# TLM_002_INA228.net
KiCad netlist of a schematic drawn in Altium Designer
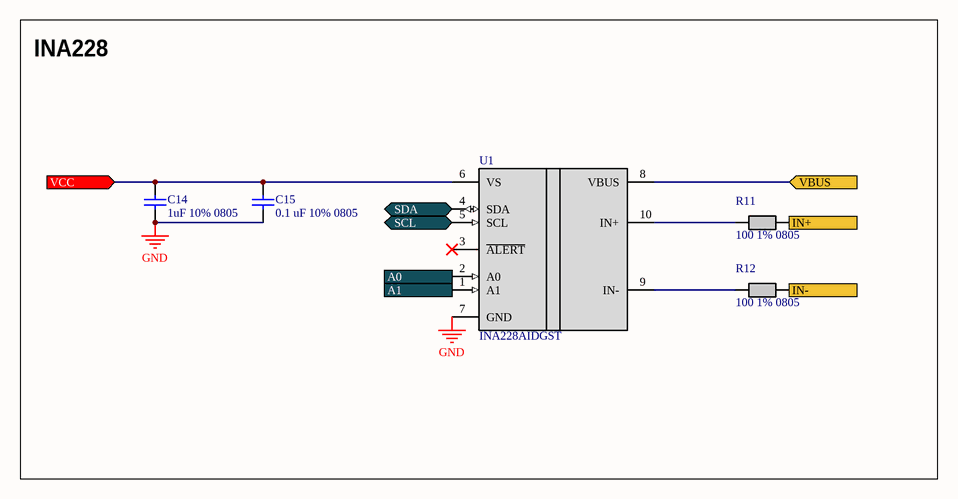
[diagram p0: TLM_002_INA228.SchDoc]

(export (version "E")
  (design (tool "Eeschema 10.0.6"))
  (components
    (comp (ref "C14")
      (value "1uF 10% 0805")
      (footprint "CAPC2013X145X50NL20T20")
      (fields (field (name "PART NUMBER") "VJ0805Y105KXQRW1BC") (field (name "MANUFACTURER") "Vitramon"))
      (libsource (lib "Altium Content Vault") (part "CAP"))
    )
    (comp (ref "C15")
      (value "0.1 uF 10% 0805")
      (footprint "CAPC2013X140X50ML20T25")
      (fields
        (field (name "PART NUMBER") "0805DD104KAT2A")
        (field (name "MANUFACTURER") "AVX Interconnect / Elco")
      )
      (libsource (lib "Altium Content Vault") (part "CAP"))
    )
    (comp (ref "R11")
      (value "100 1% 0805")
      (footprint "RES_0805")
      (description "Resistor 100Ohm 1% SMD 0805 Generic")
      (fields (field (name "TOLERANCE") "1%"))
      (libsource (lib "Generic-Schematic-Library") (part "Resistor_100"))
    )
    (comp (ref "R12")
      (value "100 1% 0805")
      (footprint "RES_0805")
      (description "Resistor 100Ohm 1% SMD 0805 Generic")
      (fields (field (name "TOLERANCE") "1%"))
      (libsource (lib "Generic-Schematic-Library") (part "Resistor_100"))
    )
    (comp (ref "U1")
      (value "INA228AIDGST")
      (footprint "FP-DGS0010A-IPC_C")
      (description "IC PWR MONITOR 10VSSOP Power Supply Controller Digital Power Monitor 10-VSSOP")
      (libsource (lib "NAZAR LYSENKO") (part "1af3035f59f546649392dbf5608e80d"))
    )
  )
  (nets
    (net (code "1") (name "/A0") (class "Default")
      (node (ref "U1") (pin "2") (pinfunction "A0_2") (pintype "input"))
    )
    (net (code "2") (name "/A1") (class "Default")
      (node (ref "U1") (pin "1") (pinfunction "A1_1") (pintype "input"))
    )
    (net (code "3") (name "/IN+") (class "Default")
      (node (ref "R11") (pin "2") (pinfunction "2_2") (pintype "passive"))
    )
    (net (code "4") (name "/IN-") (class "Default")
      (node (ref "R12") (pin "2") (pinfunction "2_2") (pintype "passive"))
    )
    (net (code "5") (name "/SCL") (class "Default")
      (node (ref "U1") (pin "5") (pinfunction "SCL_5") (pintype "input"))
    )
    (net (code "6") (name "/SDA") (class "Default")
      (node (ref "U1") (pin "4") (pinfunction "SDA_4") (pintype "bidirectional"))
    )
    (net (code "7") (name "/VBUS") (class "Default")
      (node (ref "U1") (pin "8") (pinfunction "VBUS_8") (pintype "passive"))
    )
    (net (code "8") (name "/VCC") (class "Default")
      (node (ref "C14") (pin "2") (pinfunction "2_2") (pintype "passive"))
      (node (ref "C15") (pin "2") (pinfunction "2_2") (pintype "passive"))
      (node (ref "U1") (pin "6") (pinfunction "VS_6") (pintype "passive"))
    )
    (net (code "9") (name "GND") (class "Default")
      (node (ref "C14") (pin "1") (pinfunction "1_1") (pintype "passive"))
      (node (ref "C15") (pin "1") (pinfunction "1_1") (pintype "passive"))
      (node (ref "U1") (pin "7") (pinfunction "GND_7") (pintype "power_in"))
    )
    (net (code "10") (name "Net-(U1-IN+)") (class "Default")
      (node (ref "R11") (pin "1") (pinfunction "1_1") (pintype "passive"))
      (node (ref "U1") (pin "10") (pinfunction "IN+_10") (pintype "passive"))
    )
    (net (code "11") (name "Net-(U1-IN-)") (class "Default")
      (node (ref "R12") (pin "1") (pinfunction "1_1") (pintype "passive"))
      (node (ref "U1") (pin "9") (pinfunction "IN-_9") (pintype "passive"))
    )
    (net (code "12") (name "unconnected-(U1-~{ALERT}-Pad3)") (class "Default")
      (node (ref "U1") (pin "3") (pinfunction "~{ALERT}_3") (pintype "open_collector+no_connect"))
    )
  )
)
